# SATA.net
KiCad netlist of a schematic drawn in Altium Designer
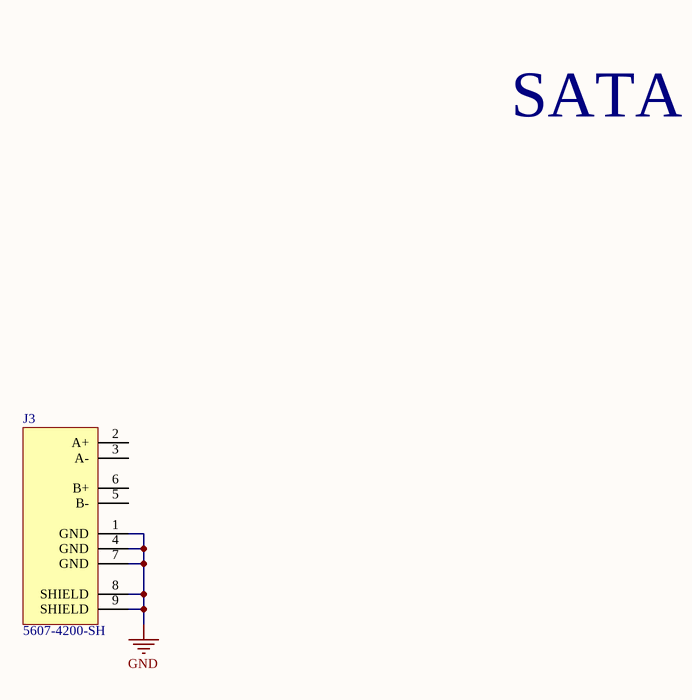
[diagram p0: SATA.SchDoc]

(export (version "E")
  (design (tool "Eeschema 10.0.6"))
  (components
    (comp (ref "J3")
      (value "5607-4200-SH")
      (footprint "5607-4200-SH")
      (description "7 Position SATA Plug Connector Solder Surface Mount, Right Angle")
      (fields (field (name "MFR") "3M") (field (name "CREATED BY") "Pascal-Emmanuel Lachance"))
      (libsource (lib "CryptLib") (part "CONN_5607-4200-SH"))
    )
  )
  (nets
    (net (code "1") (name "GND") (class "Default")
      (node (ref "J3") (pin "1") (pinfunction "GND_1") (pintype "power_in"))
      (node (ref "J3") (pin "4") (pinfunction "GND_4") (pintype "power_in"))
      (node (ref "J3") (pin "7") (pinfunction "GND_7") (pintype "power_in"))
      (node (ref "J3") (pin "8") (pinfunction "SHIELD_8") (pintype "passive"))
      (node (ref "J3") (pin "9") (pinfunction "SHIELD_9") (pintype "passive"))
    )
    (net (code "2") (name "unconnected-(J3-A+-Pad2)") (class "Default")
      (node (ref "J3") (pin "2") (pinfunction "A+_2") (pintype "passive"))
    )
    (net (code "3") (name "unconnected-(J3-A--Pad3)") (class "Default")
      (node (ref "J3") (pin "3") (pinfunction "A-_3") (pintype "passive"))
    )
    (net (code "4") (name "unconnected-(J3-B+-Pad6)") (class "Default")
      (node (ref "J3") (pin "6") (pinfunction "B+_6") (pintype "passive"))
    )
    (net (code "5") (name "unconnected-(J3-B--Pad5)") (class "Default")
      (node (ref "J3") (pin "5") (pinfunction "B-_5") (pintype "passive"))
    )
  )
)
